# SparkFun_ZED-F9R_v12_uFL.net
KiCad netlist of a schematic drawn in EAGLE
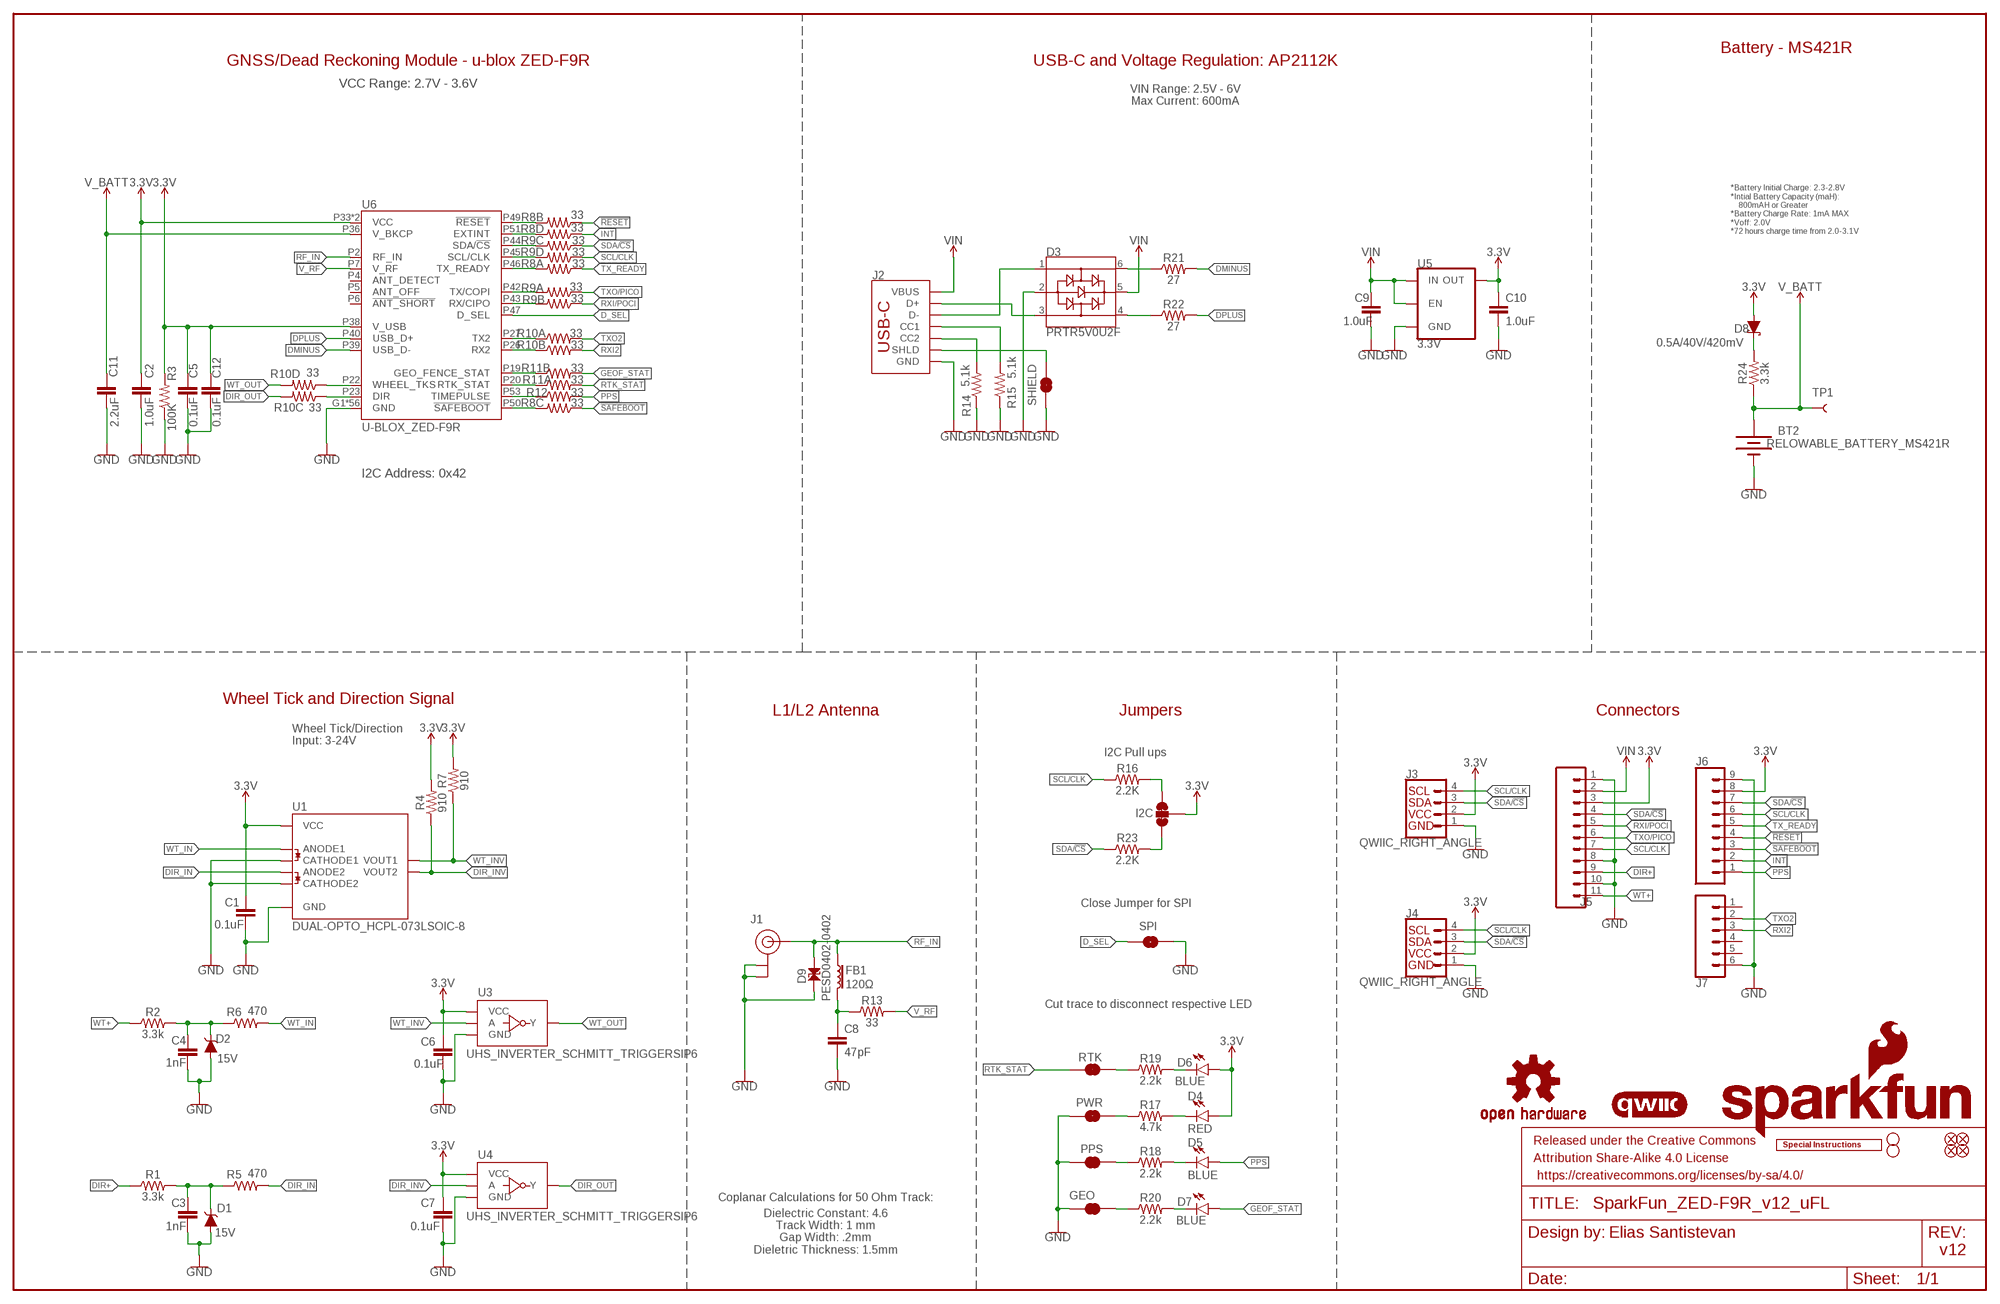
[diagram p0: schematic, sheet 1]

(export (version "E")
  (design (tool "Eeschema 10.0.6"))
  (components
    (comp (ref "$1_25_$_2020-03-30_22-52-05")
      (value "STAND-OFFTIGHT")
      (footprint "eagle-import:STAND-OFF-TIGHT")
      (libsource (lib "eagle-import") (part "STAND-OFFTIGHT"))
    )
    (comp (ref "BT2")
      (value "RELOWABLE_BATTERY_MS421R")
      (footprint "eagle-import:MS421R_IV03E")
      (libsource (lib "eagle-import") (part "RELOWABLE_BATTERY_MS421R"))
    )
    (comp (ref "C1")
      (value "0.1uF")
      (footprint "eagle-import:0402-TIGHT")
      (libsource (lib "eagle-import") (part "0.1UF-0402T-6.3V-10%-X7R"))
    )
    (comp (ref "C2")
      (value "1.0uF")
      (footprint "eagle-import:0402-TIGHT")
      (libsource (lib "eagle-import") (part "1.0UF-0402T-16V-10%"))
    )
    (comp (ref "C3")
      (value "1nF")
      (footprint "eagle-import:0402")
      (libsource (lib "eagle-import") (part "1.0NF/1000PF-0402-25V-10%-X7R"))
    )
    (comp (ref "C4")
      (value "1nF")
      (footprint "eagle-import:0402")
      (libsource (lib "eagle-import") (part "1.0NF/1000PF-0402-25V-10%-X7R"))
    )
    (comp (ref "C5")
      (value "0.1uF")
      (footprint "eagle-import:0402-TIGHT")
      (libsource (lib "eagle-import") (part "0.1UF-0402T-6.3V-10%-X7R"))
    )
    (comp (ref "C6")
      (value "0.1uF")
      (footprint "eagle-import:0402-TIGHT")
      (libsource (lib "eagle-import") (part "0.1UF-0402T-6.3V-10%-X7R"))
    )
    (comp (ref "C7")
      (value "0.1uF")
      (footprint "eagle-import:0402-TIGHT")
      (libsource (lib "eagle-import") (part "0.1UF-0402T-6.3V-10%-X7R"))
    )
    (comp (ref "C8")
      (value "47pF")
      (footprint "eagle-import:0402")
      (libsource (lib "eagle-import") (part "47PF-0402-25V-5%-X7R"))
    )
    (comp (ref "C9")
      (value "1.0uF")
      (footprint "eagle-import:0402-TIGHT")
      (libsource (lib "eagle-import") (part "1.0UF-0402T-16V-10%"))
    )
    (comp (ref "C10")
      (value "1.0uF")
      (footprint "eagle-import:0402-TIGHT")
      (libsource (lib "eagle-import") (part "1.0UF-0402T-16V-10%"))
    )
    (comp (ref "C11")
      (value "2.2uF")
      (footprint "eagle-import:0402-TIGHT")
      (libsource (lib "eagle-import") (part "2.2UF-0402_TIGHT-10V-10%-X5R"))
    )
    (comp (ref "C12")
      (value "0.1uF")
      (footprint "eagle-import:0402-TIGHT")
      (libsource (lib "eagle-import") (part "0.1UF-0402T-6.3V-10%-X7R"))
    )
    (comp (ref "D1")
      (value "15V")
      (footprint "eagle-import:SOT23-3")
      (libsource (lib "eagle-import") (part "DIODE-ZENER-BZX84C15LT3G"))
    )
    (comp (ref "D2")
      (value "15V")
      (footprint "eagle-import:SOT23-3")
      (libsource (lib "eagle-import") (part "DIODE-ZENER-BZX84C15LT3G"))
    )
    (comp (ref "D3")
      (value "PRTR5V0U2F")
      (footprint "eagle-import:SOT886")
      (libsource (lib "eagle-import") (part "PRTR5V0U2F"))
    )
    (comp (ref "D4")
      (value "RED")
      (footprint "eagle-import:LED-0603")
      (libsource (lib "eagle-import") (part "LED-RED_0603-KB"))
    )
    (comp (ref "D5")
      (value "BLUE")
      (footprint "eagle-import:LED-0603")
      (libsource (lib "eagle-import") (part "LED-BLUE0603"))
    )
    (comp (ref "D6")
      (value "BLUE")
      (footprint "eagle-import:LED-0603")
      (libsource (lib "eagle-import") (part "LED-BLUE0603"))
    )
    (comp (ref "D7")
      (value "BLUE")
      (footprint "eagle-import:LED-0603")
      (libsource (lib "eagle-import") (part "LED-BLUE0603"))
    )
    (comp (ref "D8")
      (value "0.5A/40V/420mV")
      (footprint "eagle-import:SOD-323")
      (libsource (lib "eagle-import") (part "DIODE-SCHOTTKY-PMEG4005EJ"))
    )
    (comp (ref "D9")
      (value "PESD0402-0402")
      (footprint "eagle-import:0402")
      (fields
        (field (name "DIGIKEY_PART") "PESD0402-140CT-ND")
        (field (name "MOUSE_PART") "650-PESD0402-140")
      )
      (libsource (lib "eagle-import") (part "PESD0402-0402"))
    )
    (comp (ref "FB1")
      (value "120Ω")
      (footprint "eagle-import:0402")
      (fields (field (name "MFG_PART") "BLM15HB121SN1D"))
      (libsource (lib "eagle-import") (part "FERRITE_BEAD-120_OHM-0402"))
    )
    (comp (ref "FD1")
      (value "FIDUCIALUFIDUCIAL")
      (footprint "eagle-import:FIDUCIAL-MICRO")
      (libsource (lib "eagle-import") (part "FIDUCIALUFIDUCIAL"))
    )
    (comp (ref "FD2")
      (value "FIDUCIALUFIDUCIAL")
      (footprint "eagle-import:FIDUCIAL-MICRO")
      (libsource (lib "eagle-import") (part "FIDUCIALUFIDUCIAL"))
    )
    (comp (ref "FD3")
      (value "FIDUCIALUFIDUCIAL")
      (footprint "eagle-import:FIDUCIAL-MICRO")
      (libsource (lib "eagle-import") (part "FIDUCIALUFIDUCIAL"))
    )
    (comp (ref "FD4")
      (value "FIDUCIALUFIDUCIAL")
      (footprint "eagle-import:FIDUCIAL-MICRO")
      (libsource (lib "eagle-import") (part "FIDUCIALUFIDUCIAL"))
    )
    (comp (ref "FRAME1")
      (value "FRAME-LEDGER")
      (footprint "eagle-import:CREATIVE_COMMONS")
      (libsource (lib "eagle-import") (part "FRAME-LEDGER"))
    )
    (comp (ref "GEO")
      (value "JUMPER-SMT_2_NC_TRACE_SILK")
      (footprint "eagle-import:SMT-JUMPER_2_NC_TRACE_SILK")
      (libsource (lib "eagle-import") (part "JUMPER-SMT_2_NC_TRACE_SILK"))
    )
    (comp (ref "H2")
      (value "STAND-OFFTIGHT")
      (footprint "eagle-import:STAND-OFF-TIGHT")
      (libsource (lib "eagle-import") (part "STAND-OFFTIGHT"))
    )
    (comp (ref "I2C")
      (value "JUMPER-SMT_3_2-NC_TRACE_SILK")
      (footprint "eagle-import:SMT-JUMPER_3_2-NC_TRACE_SILK")
      (libsource (lib "eagle-import") (part "JUMPER-SMT_3_2-NC_TRACE_SILK"))
    )
    (comp (ref "J1")
      (value "U.FL")
      (footprint "eagle-import:U.FL")
      (libsource (lib "eagle-import") (part "U.FL"))
    )
    (comp (ref "J2")
      (value "USB_C_2-LAYER_PADS")
      (footprint "eagle-import:USB-C-16P-2LAYER-PADS")
      (libsource (lib "eagle-import") (part "USB_C_2-LAYER_PADS"))
    )
    (comp (ref "J3")
      (value "QWIIC_RIGHT_ANGLE")
      (footprint "eagle-import:JST04_1MM_RA")
      (libsource (lib "eagle-import") (part "QWIIC_CONNECTORJS-1MM"))
    )
    (comp (ref "J4")
      (value "QWIIC_RIGHT_ANGLE")
      (footprint "eagle-import:JST04_1MM_RA")
      (libsource (lib "eagle-import") (part "QWIIC_CONNECTORJS-1MM"))
    )
    (comp (ref "J5")
      (value "CONN_111X11_NO_SILK")
      (footprint "eagle-import:1X11_NO_SILK")
      (libsource (lib "eagle-import") (part "CONN_111X11_NO_SILK"))
    )
    (comp (ref "J6")
      (value "CONN_09NO_SILK")
      (footprint "eagle-import:1X09_NO_SILK")
      (libsource (lib "eagle-import") (part "CONN_09NO_SILK"))
    )
    (comp (ref "J7")
      (value "CONN_06NO_SILK_NO_POP")
      (footprint "eagle-import:1X06_NO_SILK")
      (libsource (lib "eagle-import") (part "CONN_06NO_SILK_NO_POP"))
    )
    (comp (ref "LOGO1")
      (value "OSHW-LOGOS")
      (footprint "eagle-import:OSHW-LOGO-S")
      (libsource (lib "eagle-import") (part "OSHW-LOGOS"))
    )
    (comp (ref "LOGO2")
      (value "QWIIC_LOGO_4MM")
      (footprint "eagle-import:QWIIC_4MM")
      (libsource (lib "eagle-import") (part "QWIIC_LOGO_4MM"))
    )
    (comp (ref "LOGO3")
      (value "SFE_LOGO_NAME_FLAME.2_INCH")
      (footprint "eagle-import:SFE_LOGO_NAME_FLAME_.2")
      (libsource (lib "eagle-import") (part "SFE_LOGO_NAME_FLAME.2_INCH"))
    )
    (comp (ref "LOGO5")
      (value "SPECIAL_INSTRUCTIONS-ORDERING")
      (footprint "eagle-import:ORDERING_INSTRUCTIONS")
      (libsource (lib "eagle-import") (part "SPECIAL_INSTRUCTIONS-ORDERING"))
    )
    (comp (ref "PPS")
      (value "JUMPER-SMT_2_NC_TRACE_SILK")
      (footprint "eagle-import:SMT-JUMPER_2_NC_TRACE_SILK")
      (libsource (lib "eagle-import") (part "JUMPER-SMT_2_NC_TRACE_SILK"))
    )
    (comp (ref "PWR")
      (value "JUMPER-SMT_2_NC_TRACE_SILK")
      (footprint "eagle-import:SMT-JUMPER_2_NC_TRACE_SILK")
      (libsource (lib "eagle-import") (part "JUMPER-SMT_2_NC_TRACE_SILK"))
    )
    (comp (ref "R1")
      (value "3.3k")
      (footprint "eagle-import:0603")
      (libsource (lib "eagle-import") (part "3.3KOHM-0603-1/10W-1%"))
    )
    (comp (ref "R2")
      (value "3.3k")
      (footprint "eagle-import:0603")
      (libsource (lib "eagle-import") (part "3.3KOHM-0603-1/10W-1%"))
    )
    (comp (ref "R3")
      (value "100K")
      (footprint "eagle-import:0402")
      (libsource (lib "eagle-import") (part "100KOHM-0402-1/16W-1%"))
    )
    (comp (ref "R4")
      (value "910")
      (footprint "eagle-import:0603")
      (libsource (lib "eagle-import") (part "910OHM-0603-1/10W-5%"))
    )
    (comp (ref "R5")
      (value "470")
      (footprint "eagle-import:0603")
      (libsource (lib "eagle-import") (part "470OHM-0603-1/10W-1%"))
    )
    (comp (ref "R6")
      (value "470")
      (footprint "eagle-import:0603")
      (libsource (lib "eagle-import") (part "470OHM-0603-1/10W-1%"))
    )
    (comp (ref "R7")
      (value "910")
      (footprint "eagle-import:0603")
      (libsource (lib "eagle-import") (part "910OHM-0603-1/10W-5%"))
    )
    (comp (ref "R8")
      (value "33")
      (footprint "eagle-import:1206_RA")
      (libsource (lib "eagle-import") (part "33OHM_RA-1206-1/16W-5%"))
    )
    (comp (ref "R9")
      (value "33")
      (footprint "eagle-import:1206_RA")
      (libsource (lib "eagle-import") (part "33OHM_RA-1206-1/16W-5%"))
    )
    (comp (ref "R10")
      (value "33")
      (footprint "eagle-import:1206_RA")
      (libsource (lib "eagle-import") (part "33OHM_RA-1206-1/16W-5%"))
    )
    (comp (ref "R11")
      (value "33")
      (footprint "eagle-import:1206_RA")
      (libsource (lib "eagle-import") (part "33OHM_RA-1206-1/16W-5%"))
    )
    (comp (ref "R12")
      (value "33")
      (footprint "eagle-import:0603")
      (libsource (lib "eagle-import") (part "33OHM-0603-1/10W-1%"))
    )
    (comp (ref "R13")
      (value "33")
      (footprint "eagle-import:0603")
      (libsource (lib "eagle-import") (part "33OHM-0603-1/10W-1%"))
    )
    (comp (ref "R14")
      (value "5.1k")
      (footprint "eagle-import:0402")
      (libsource (lib "eagle-import") (part "5.1KOHM-0402-1/16W-1%"))
    )
    (comp (ref "R15")
      (value "5.1k")
      (footprint "eagle-import:0402")
      (libsource (lib "eagle-import") (part "5.1KOHM-0402-1/16W-1%"))
    )
    (comp (ref "R16")
      (value "2.2K")
      (footprint "eagle-import:0402")
      (libsource (lib "eagle-import") (part "2.2KOHM-0402-1/16W-1%"))
    )
    (comp (ref "R17")
      (value "4.7k")
      (footprint "eagle-import:0603")
      (libsource (lib "eagle-import") (part "4.7KOHM-0603-1/10W-1%"))
    )
    (comp (ref "R18")
      (value "2.2k")
      (footprint "eagle-import:0603")
      (libsource (lib "eagle-import") (part "2.2KOHM-0603-1/10W-1%"))
    )
    (comp (ref "R19")
      (value "2.2k")
      (footprint "eagle-import:0603")
      (libsource (lib "eagle-import") (part "2.2KOHM-0603-1/10W-1%"))
    )
    (comp (ref "R20")
      (value "2.2k")
      (footprint "eagle-import:0603")
      (libsource (lib "eagle-import") (part "2.2KOHM-0603-1/10W-1%"))
    )
    (comp (ref "R21")
      (value "27")
      (footprint "eagle-import:0603")
      (libsource (lib "eagle-import") (part "27OHM-0603-1/10W-1%"))
    )
    (comp (ref "R22")
      (value "27")
      (footprint "eagle-import:0603")
      (libsource (lib "eagle-import") (part "27OHM-0603-1/10W-1%"))
    )
    (comp (ref "R23")
      (value "2.2K")
      (footprint "eagle-import:0402")
      (libsource (lib "eagle-import") (part "2.2KOHM-0402-1/16W-1%"))
    )
    (comp (ref "R24")
      (value "3.3k")
      (footprint "eagle-import:0603")
      (libsource (lib "eagle-import") (part "3.3KOHM-0603-1/10W-1%"))
    )
    (comp (ref "RTK")
      (value "JUMPER-SMT_2_NC_TRACE_SILK")
      (footprint "eagle-import:SMT-JUMPER_2_NC_TRACE_SILK")
      (libsource (lib "eagle-import") (part "JUMPER-SMT_2_NC_TRACE_SILK"))
    )
    (comp (ref "SHIELD")
      (value "JUMPER-SMT_2_NC_TRACE_SILK")
      (footprint "eagle-import:SMT-JUMPER_2_NC_TRACE_SILK")
      (libsource (lib "eagle-import") (part "JUMPER-SMT_2_NC_TRACE_SILK"))
    )
    (comp (ref "SPI")
      (value "JUMPER-SMT_2_NO_SILK")
      (footprint "eagle-import:SMT-JUMPER_2_NO_SILK")
      (libsource (lib "eagle-import") (part "JUMPER-SMT_2_NO_SILK"))
    )
    (comp (ref "TP1")
      (value "TEST-POINT3X5")
      (footprint "eagle-import:PAD.03X.05")
      (libsource (lib "eagle-import") (part "TEST-POINT3X5"))
    )
    (comp (ref "U1")
      (value "DUAL-OPTO_HCPL-073LSOIC-8")
      (footprint "eagle-import:SO08")
      (libsource (lib "eagle-import") (part "DUAL-OPTO_HCPL-073LSOIC-8"))
    )
    (comp (ref "U3")
      (value "UHS_INVERTER_SCHMITT_TRIGGERSIP6")
      (footprint "eagle-import:SIP6_MICROPAK2")
      (libsource (lib "eagle-import") (part "UHS_INVERTER_SCHMITT_TRIGGER_MPAK2"))
    )
    (comp (ref "U4")
      (value "UHS_INVERTER_SCHMITT_TRIGGERSIP6")
      (footprint "eagle-import:SIP6_MICROPAK2")
      (libsource (lib "eagle-import") (part "UHS_INVERTER_SCHMITT_TRIGGER_MPAK2"))
    )
    (comp (ref "U5")
      (value "3.3V")
      (footprint "eagle-import:SOT23-5")
      (libsource (lib "eagle-import") (part "V_REG_AP2112K-3.3V"))
    )
    (comp (ref "U6")
      (value "U-BLOX_ZED-F9R")
      (footprint "eagle-import:UBLOX_ZED_F9R")
      (libsource (lib "eagle-import") (part "U-BLOX_ZED-F9R"))
    )
  )
  (nets
    (net (code "1") (name "/SDA{slash}~{CS}") (class "Default")
      (node (ref "J3") (pin "3") (pinfunction "3_3") (pintype "passive"))
      (node (ref "J4") (pin "3") (pinfunction "3_3") (pintype "passive"))
      (node (ref "J5") (pin "4") (pinfunction "4_4") (pintype "passive"))
      (node (ref "J6") (pin "7") (pinfunction "7_7") (pintype "passive"))
      (node (ref "R23") (pin "1") (pinfunction "1_1") (pintype "passive"))
      (node (ref "R9") (pin "P3") (pinfunction "1_P3") (pintype "passive"))
    )
    (net (code "2") (name "/~{RESET}") (class "Default")
      (node (ref "J6") (pin "4") (pinfunction "4_4") (pintype "passive"))
      (node (ref "R8") (pin "P2") (pinfunction "1_P2") (pintype "passive"))
    )
    (net (code "3") (name "/~{SAFEBOOT}") (class "Default")
      (node (ref "J6") (pin "3") (pinfunction "3_3") (pintype "passive"))
      (node (ref "R8") (pin "P3") (pinfunction "1_P3") (pintype "passive"))
    )
    (net (code "4") (name "3.3V") (class "Default")
      (node (ref "C1") (pin "1") (pinfunction "1_1") (pintype "passive"))
      (node (ref "C10") (pin "1") (pinfunction "1_1") (pintype "passive"))
      (node (ref "C12") (pin "1") (pinfunction "1_1") (pintype "passive"))
      (node (ref "C2") (pin "1") (pinfunction "1_1") (pintype "passive"))
      (node (ref "C5") (pin "1") (pinfunction "1_1") (pintype "passive"))
      (node (ref "C6") (pin "1") (pinfunction "1_1") (pintype "passive"))
      (node (ref "C7") (pin "1") (pinfunction "1_1") (pintype "passive"))
      (node (ref "D4") (pin "A") (pinfunction "A_A") (pintype "passive"))
      (node (ref "D6") (pin "A") (pinfunction "A_A") (pintype "passive"))
      (node (ref "D8") (pin "A") (pinfunction "A_A") (pintype "passive"))
      (node (ref "I2C") (pin "2") (pinfunction "2_2") (pintype "passive"))
      (node (ref "J3") (pin "2") (pinfunction "2_2") (pintype "power_in"))
      (node (ref "J4") (pin "2") (pinfunction "2_2") (pintype "power_in"))
      (node (ref "J5") (pin "3") (pinfunction "3_3") (pintype "passive"))
      (node (ref "J6") (pin "8") (pinfunction "8_8") (pintype "passive"))
      (node (ref "R3") (pin "2") (pinfunction "2_2") (pintype "passive"))
      (node (ref "R4") (pin "2") (pinfunction "2_2") (pintype "passive"))
      (node (ref "R7") (pin "2") (pinfunction "2_2") (pintype "passive"))
      (node (ref "U1") (pin "8") (pinfunction "VCC_8") (pintype "power_in"))
      (node (ref "U3") (pin "P6") (pinfunction "VCC_P6") (pintype "power_in"))
      (node (ref "U4") (pin "P6") (pinfunction "VCC_P6") (pintype "power_in"))
      (node (ref "U5") (pin "5") (pinfunction "OUT_5") (pintype "passive"))
      (node (ref "U6") (pin "P33") (pinfunction "VCC_P33") (pintype "power_in"))
      (node (ref "U6") (pin "P34") (pinfunction "VCC_P34") (pintype "power_in"))
      (node (ref "U6") (pin "P38") (pinfunction "V_USB_P38") (pintype "power_in"))
    )
    (net (code "5") (name "DIR+") (class "Default")
      (node (ref "J5") (pin "9") (pinfunction "9_9") (pintype "passive"))
      (node (ref "R1") (pin "1") (pinfunction "1_1") (pintype "passive"))
    )
    (net (code "6") (name "DIR_IN") (class "Default")
      (node (ref "R5") (pin "2") (pinfunction "2_2") (pintype "passive"))
      (node (ref "U1") (pin "4") (pinfunction "ANODE2_4") (pintype "input"))
    )
    (net (code "7") (name "DIR_INV") (class "Default")
      (node (ref "R4") (pin "1") (pinfunction "1_1") (pintype "passive"))
      (node (ref "U1") (pin "6") (pinfunction "VOUT2_6") (pintype "output"))
      (node (ref "U4") (pin "P2") (pinfunction "A_P2") (pintype "input"))
    )
    (net (code "8") (name "DIR_OUT") (class "Default")
      (node (ref "R10") (pin "P6") (pinfunction "2_P6") (pintype "passive"))
      (node (ref "U4") (pin "P4") (pinfunction "Y_P4") (pintype "output"))
    )
    (net (code "9") (name "DMINUS") (class "Default")
      (node (ref "R21") (pin "2") (pinfunction "2_2") (pintype "passive"))
      (node (ref "U6") (pin "P39") (pinfunction "USB_D-_P39") (pintype "bidirectional"))
    )
    (net (code "10") (name "DPLUS") (class "Default")
      (node (ref "R22") (pin "2") (pinfunction "2_2") (pintype "passive"))
      (node (ref "U6") (pin "P40") (pinfunction "USB_D+_P40") (pintype "bidirectional"))
    )
    (net (code "11") (name "D_SEL") (class "Default")
      (node (ref "SPI") (pin "1") (pinfunction "1_1") (pintype "passive"))
      (node (ref "U6") (pin "P47") (pinfunction "D_SEL_P47") (pintype "bidirectional"))
    )
    (net (code "12") (name "GEOF_STAT") (class "Default")
      (node (ref "D7") (pin "A") (pinfunction "A_A") (pintype "passive"))
      (node (ref "R11") (pin "P7") (pinfunction "2_P7") (pintype "passive"))
    )
    (net (code "13") (name "GND") (class "Default")
      (node (ref "BT2") (pin "-") (pinfunction "-_-") (pintype "power_in"))
      (node (ref "C1") (pin "2") (pinfunction "2_2") (pintype "passive"))
      (node (ref "C10") (pin "2") (pinfunction "2_2") (pintype "passive"))
      (node (ref "C11") (pin "2") (pinfunction "2_2") (pintype "passive"))
      (node (ref "C12") (pin "2") (pinfunction "2_2") (pintype "passive"))
      (node (ref "C2") (pin "2") (pinfunction "2_2") (pintype "passive"))
      (node (ref "C3") (pin "2") (pinfunction "2_2") (pintype "passive"))
      (node (ref "C4") (pin "2") (pinfunction "2_2") (pintype "passive"))
      (node (ref "C5") (pin "2") (pinfunction "2_2") (pintype "passive"))
      (node (ref "C6") (pin "2") (pinfunction "2_2") (pintype "passive"))
      (node (ref "C7") (pin "2") (pinfunction "2_2") (pintype "passive"))
      (node (ref "C8") (pin "2") (pinfunction "2_2") (pintype "passive"))
      (node (ref "C9") (pin "2") (pinfunction "2_2") (pintype "passive"))
      (node (ref "D1") (pin "1") (pinfunction "A_1") (pintype "passive"))
      (node (ref "D2") (pin "1") (pinfunction "A_1") (pintype "passive"))
      (node (ref "D3") (pin "2") (pinfunction "2_2") (pintype "power_in"))
      (node (ref "D9") (pin "1") (pinfunction "1_1") (pintype "bidirectional"))
      (node (ref "GEO") (pin "1") (pinfunction "1_1") (pintype "passive"))
      (node (ref "J1") (pin "1") (pinfunction "GND_1") (pintype "bidirectional"))
      (node (ref "J1") (pin "2") (pinfunction "GND_2") (pintype "bidirectional"))
      (node (ref "J2") (pin "GND") (pinfunction "GND_GND") (pintype "bidirectional"))
      (node (ref "J2") (pin "GND2") (pinfunction "GND_GND2") (pintype "bidirectional"))
      (node (ref "J3") (pin "1") (pinfunction "1_1") (pintype "power_in"))
      (node (ref "J4") (pin "1") (pinfunction "1_1") (pintype "power_in"))
      (node (ref "J5") (pin "1") (pinfunction "1_1") (pintype "passive"))
      (node (ref "J5") (pin "10") (pinfunction "10_10") (pintype "passive"))
      (node (ref "J5") (pin "8") (pinfunction "8_8") (pintype "passive"))
      (node (ref "J6") (pin "9") (pinfunction "9_9") (pintype "passive"))
      (node (ref "J7") (pin "6") (pinfunction "6_6") (pintype "passive"))
      (node (ref "PPS") (pin "1") (pinfunction "1_1") (pintype "passive"))
      (node (ref "PWR") (pin "1") (pinfunction "1_1") (pintype "passive"))
      (node (ref "R14") (pin "1") (pinfunction "1_1") (pintype "passive"))
      (node (ref "R15") (pin "1") (pinfunction "1_1") (pintype "passive"))
      (node (ref "R3") (pin "1") (pinfunction "1_1") (pintype "passive"))
      (node (ref "SHIELD") (pin "1") (pinfunction "1_1") (pintype "passive"))
      (node (ref "SPI") (pin "2") (pinfunction "2_2") (pintype "passive"))
      (node (ref "U1") (pin "2") (pinfunction "CATHODE1_2") (pintype "input"))
      (node (ref "U1") (pin "3") (pinfunction "CATHODE2_3") (pintype "input"))
      (node (ref "U1") (pin "5") (pinfunction "GND_5") (pintype "power_in"))
      (node (ref "U3") (pin "P3") (pinfunction "GND_P3") (pintype "power_in"))
      (node (ref "U4") (pin "P3") (pinfunction "GND_P3") (pintype "power_in"))
      (node (ref "U5") (pin "2") (pinfunction "GND_2") (pintype "input"))
      (node (ref "U6") (pin "G1") (pinfunction "GND_G1") (pintype "power_in"))
      (node (ref "U6") (pin "G10") (pinfunction "GND_G10") (pintype "power_in"))
      (node (ref "U6") (pin "G11") (pinfunction "GND_G11") (pintype "power_in"))
      (node (ref "U6") (pin "G12") (pinfunction "GND_G12") (pintype "power_in"))
      (node (ref "U6") (pin "G13") (pinfunction "GND_G13") (pintype "power_in"))
      (node (ref "U6") (pin "G14") (pinfunction "GND_G14") (pintype "power_in"))
      (node (ref "U6") (pin "G15") (pinfunction "GND_G15") (pintype "power_in"))
      (node (ref "U6") (pin "G16") (pinfunction "GND_G16") (pintype "power_in"))
      (node (ref "U6") (pin "G17") (pinfunction "GND_G17") (pintype "power_in"))
      (node (ref "U6") (pin "G18") (pinfunction "GND_G18") (pintype "power_in"))
      (node (ref "U6") (pin "G19") (pinfunction "GND_G19") (pintype "power_in"))
      (node (ref "U6") (pin "G2") (pinfunction "GND_G2") (pintype "power_in"))
      (node (ref "U6") (pin "G20") (pinfunction "GND_G20") (pintype "power_in"))
      (node (ref "U6") (pin "G21") (pinfunction "GND_G21") (pintype "power_in"))
      (node (ref "U6") (pin "G22") (pinfunction "GND_G22") (pintype "power_in"))
      (node (ref "U6") (pin "G23") (pinfunction "GND_G23") (pintype "power_in"))
      (node (ref "U6") (pin "G24") (pinfunction "GND_G24") (pintype "power_in"))
      (node (ref "U6") (pin "G25") (pinfunction "GND_G25") (pintype "power_in"))
      (node (ref "U6") (pin "G26") (pinfunction "GND_G26") (pintype "power_in"))
      (node (ref "U6") (pin "G27") (pinfunction "GND_G27") (pintype "power_in"))
      (node (ref "U6") (pin "G28") (pinfunction "GND_G28") (pintype "power_in"))
      (node (ref "U6") (pin "G29") (pinfunction "GND_G29") (pintype "power_in"))
      (node (ref "U6") (pin "G3") (pinfunction "GND_G3") (pintype "power_in"))
      (node (ref "U6") (pin "G30") (pinfunction "GND_G30") (pintype "power_in"))
      (node (ref "U6") (pin "G31") (pinfunction "GND_G31") (pintype "power_in"))
      (node (ref "U6") (pin "G32") (pinfunction "GND_G32") (pintype "power_in"))
      (node (ref "U6") (pin "G33") (pinfunction "GND_G33") (pintype "power_in"))
      (node (ref "U6") (pin "G34") (pinfunction "GND_G34") (pintype "power_in"))
      (node (ref "U6") (pin "G35") (pinfunction "GND_G35") (pintype "power_in"))
      (node (ref "U6") (pin "G36") (pinfunction "GND_G36") (pintype "power_in"))
      (node (ref "U6") (pin "G37") (pinfunction "GND_G37") (pintype "power_in"))
      (node (ref "U6") (pin "G38") (pinfunction "GND_G38") (pintype "power_in"))
      (node (ref "U6") (pin "G39") (pinfunction "GND_G39") (pintype "power_in"))
      (node (ref "U6") (pin "G4") (pinfunction "GND_G4") (pintype "power_in"))
      (node (ref "U6") (pin "G40") (pinfunction "GND_G40") (pintype "power_in"))
      (node (ref "U6") (pin "G41") (pinfunction "GND_G41") (pintype "power_in"))
      (node (ref "U6") (pin "G42") (pinfunction "GND_G42") (pintype "power_in"))
      (node (ref "U6") (pin "G43") (pinfunction "GND_G43") (pintype "power_in"))
      (node (ref "U6") (pin "G44") (pinfunction "GND_G44") (pintype "power_in"))
      (node (ref "U6") (pin "G45") (pinfunction "GND_G45") (pintype "power_in"))
      (node (ref "U6") (pin "G46") (pinfunction "GND_G46") (pintype "power_in"))
      (node (ref "U6") (pin "G47") (pinfunction "GND_G47") (pintype "power_in"))
      (node (ref "U6") (pin "G48") (pinfunction "GND_G48") (pintype "power_in"))
      (node (ref "U6") (pin "G5") (pinfunction "GND_G5") (pintype "power_in"))
      (node (ref "U6") (pin "G6") (pinfunction "GND_G6") (pintype "power_in"))
      (node (ref "U6") (pin "G7") (pinfunction "GND_G7") (pintype "power_in"))
      (node (ref "U6") (pin "G8") (pinfunction "GND_G8") (pintype "power_in"))
      (node (ref "U6") (pin "G9") (pinfunction "GND_G9") (pintype "power_in"))
      (node (ref "U6") (pin "P1") (pinfunction "GND_P1") (pintype "power_in"))
      (node (ref "U6") (pin "P12") (pinfunction "GND_P12") (pintype "power_in"))
      (node (ref "U6") (pin "P14") (pinfunction "GND_P14") (pintype "power_in"))
      (node (ref "U6") (pin "P3") (pinfunction "GND_P3") (pintype "power_in"))
      (node (ref "U6") (pin "P32") (pinfunction "GND_P32") (pintype "power_in"))
      (node (ref "U6") (pin "P37") (pinfunction "GND_P37") (pintype "power_in"))
      (node (ref "U6") (pin "P41") (pinfunction "GND_P41") (pintype "power_in"))
      (node (ref "U6") (pin "P48") (pinfunction "GND_P48") (pintype "power_in"))
    )
    (net (code "14") (name "INT") (class "Default")
      (node (ref "J6") (pin "2") (pinfunction "2_2") (pintype "passive"))
      (node (ref "R8") (pin "P4") (pinfunction "1_P4") (pintype "passive"))
    )
    (net (code "15") (name "Net-(C8-Pad1)") (class "Default")
      (node (ref "C8") (pin "1") (pinfunction "1_1") (pintype "passive"))
      (node (ref "FB1") (pin "2") (pinfunction "2_2") (pintype "passive"))
      (node (ref "R13") (pin "1") (pinfunction "1_1") (pintype "passive"))
    )
    (net (code "16") (name "Net-(D1-C)") (class "Default")
      (node (ref "C3") (pin "1") (pinfunction "1_1") (pintype "passive"))
      (node (ref "D1") (pin "3") (pinfunction "C_3") (pintype "passive"))
      (node (ref "R1") (pin "2") (pinfunction "2_2") (pintype "passive"))
      (node (ref "R5") (pin "1") (pinfunction "1_1") (pintype "passive"))
    )
    (net (code "17") (name "Net-(D2-C)") (class "Default")
      (node (ref "C4") (pin "1") (pinfunction "1_1") (pintype "passive"))
      (node (ref "D2") (pin "3") (pinfunction "C_3") (pintype "passive"))
      (node (ref "R2") (pin "2") (pinfunction "2_2") (pintype "passive"))
      (node (ref "R6") (pin "1") (pinfunction "1_1") (pintype "passive"))
    )
    (net (code "18") (name "Net-(D3-Pad1)") (class "Default")
      (node (ref "D3") (pin "1") (pinfunction "1_1") (pintype "bidirectional"))
      (node (ref "J2") (pin "A7") (pinfunction "D-_A7") (pintype "bidirectional"))
      (node (ref "J2") (pin "B7") (pinfunction "D-_B7") (pintype "bidirectional"))
    )
    (net (code "19") (name "Net-(D3-Pad3)") (class "Default")
      (node (ref "D3") (pin "3") (pinfunction "3_3") (pintype "bidirectional"))
      (node (ref "J2") (pin "A6") (pinfunction "D+_A6") (pintype "bidirectional"))
      (node (ref "J2") (pin "B6") (pinfunction "D+_B6") (pintype "bidirectional"))
    )
    (net (code "20") (name "Net-(D3-Pad4)") (class "Default")
      (node (ref "D3") (pin "4") (pinfunction "4_4") (pintype "bidirectional"))
      (node (ref "R22") (pin "1") (pinfunction "1_1") (pintype "passive"))
    )
    (net (code "21") (name "Net-(D3-Pad6)") (class "Default")
      (node (ref "D3") (pin "6") (pinfunction "6_6") (pintype "bidirectional"))
      (node (ref "R21") (pin "1") (pinfunction "1_1") (pintype "passive"))
    )
    (net (code "22") (name "Net-(D4-PadC)") (class "Default")
      (node (ref "D4") (pin "C") (pinfunction "C_C") (pintype "passive"))
      (node (ref "R17") (pin "2") (pinfunction "2_2") (pintype "passive"))
    )
    (net (code "23") (name "Net-(D5-PadC)") (class "Default")
      (node (ref "D5") (pin "C") (pinfunction "C_C") (pintype "passive"))
      (node (ref "R18") (pin "2") (pinfunction "2_2") (pintype "passive"))
    )
    (net (code "24") (name "Net-(D6-PadC)") (class "Default")
      (node (ref "D6") (pin "C") (pinfunction "C_C") (pintype "passive"))
      (node (ref "R19") (pin "2") (pinfunction "2_2") (pintype "passive"))
    )
    (net (code "25") (name "Net-(D7-PadC)") (class "Default")
      (node (ref "D7") (pin "C") (pinfunction "C_C") (pintype "passive"))
      (node (ref "R20") (pin "2") (pinfunction "2_2") (pintype "passive"))
    )
    (net (code "26") (name "Net-(D8-PadC)") (class "Default")
      (node (ref "D8") (pin "C") (pinfunction "C_C") (pintype "passive"))
      (node (ref "R24") (pin "2") (pinfunction "2_2") (pintype "passive"))
    )
    (net (code "27") (name "Net-(GEO-Pad2)") (class "Default")
      (node (ref "GEO") (pin "2") (pinfunction "2_2") (pintype "passive"))
      (node (ref "R20") (pin "1") (pinfunction "1_1") (pintype "passive"))
    )
    (net (code "28") (name "Net-(I2C-Pad1)") (class "Default")
      (node (ref "I2C") (pin "1") (pinfunction "1_1") (pintype "passive"))
      (node (ref "R23") (pin "2") (pinfunction "2_2") (pintype "passive"))
    )
    (net (code "29") (name "Net-(I2C-Pad3)") (class "Default")
      (node (ref "I2C") (pin "3") (pinfunction "3_3") (pintype "passive"))
      (node (ref "R16") (pin "2") (pinfunction "2_2") (pintype "passive"))
    )
    (net (code "30") (name "Net-(J2-CC1)") (class "Default")
      (node (ref "J2") (pin "A5") (pinfunction "CC1_A5") (pintype "bidirectional"))
      (node (ref "R15") (pin "2") (pinfunction "2_2") (pintype "passive"))
    )
    (net (code "31") (name "Net-(J2-CC2)") (class "Default")
      (node (ref "J2") (pin "B5") (pinfunction "CC2_B5") (pintype "bidirectional"))
      (node (ref "R14") (pin "2") (pinfunction "2_2") (pintype "passive"))
    )
    (net (code "32") (name "Net-(J2-SHLD-PadSHLD1)") (class "Default")
      (node (ref "J2") (pin "SHLD1") (pinfunction "SHLD_SHLD1") (pintype "bidirectional"))
      (node (ref "J2") (pin "SHLD2") (pinfunction "SHLD_SHLD2") (pintype "bidirectional"))
      (node (ref "J2") (pin "SHLD3") (pinfunction "SHLD_SHLD3") (pintype "bidirectional"))
      (node (ref "J2") (pin "SHLD4") (pinfunction "SHLD_SHLD4") (pintype "bidirectional"))
      (node (ref "SHIELD") (pin "2") (pinfunction "2_2") (pintype "passive"))
    )
    (net (code "33") (name "Net-(PPS-Pad2)") (class "Default")
      (node (ref "PPS") (pin "2") (pinfunction "2_2") (pintype "passive"))
      (node (ref "R18") (pin "1") (pinfunction "1_1") (pintype "passive"))
    )
    (net (code "34") (name "Net-(PWR-Pad2)") (class "Default")
      (node (ref "PWR") (pin "2") (pinfunction "2_2") (pintype "passive"))
      (node (ref "R17") (pin "1") (pinfunction "1_1") (pintype "passive"))
    )
    (net (code "35") (name "Net-(R8A-2)") (class "Default")
      (node (ref "R8") (pin "P8") (pinfunction "2_P8") (pintype "passive"))
      (node (ref "U6") (pin "P46") (pinfunction "TX_READY_P46") (pintype "bidirectional"))
    )
    (net (code "36") (name "Net-(R8B-2)") (class "Default")
      (node (ref "R8") (pin "P7") (pinfunction "2_P7") (pintype "passive"))
      (node (ref "U6") (pin "P49") (pinfunction "~{RESET}_P49") (pintype "bidirectional"))
    )
    (net (code "37") (name "Net-(R8C-2)") (class "Default")
      (node (ref "R8") (pin "P6") (pinfunction "2_P6") (pintype "passive"))
      (node (ref "U6") (pin "P50") (pinfunction "~{SAFEBOOT}_P50") (pintype "input"))
    )
    (net (code "38") (name "Net-(R8D-2)") (class "Default")
      (node (ref "R8") (pin "P5") (pinfunction "2_P5") (pintype "passive"))
      (node (ref "U6") (pin "P51") (pinfunction "EXTINT_P51") (pintype "bidirectional"))
    )
    (net (code "39") (name "Net-(R9A-2)") (class "Default")
      (node (ref "R9") (pin "P8") (pinfunction "2_P8") (pintype "passive"))
      (node (ref "U6") (pin "P42") (pinfunction "TX/COPI_P42") (pintype "bidirectional"))
    )
    (net (code "40") (name "Net-(R9B-2)") (class "Default")
      (node (ref "R9") (pin "P7") (pinfunction "2_P7") (pintype "passive"))
      (node (ref "U6") (pin "P43") (pinfunction "RX/CIPO_P43") (pintype "bidirectional"))
    )
    (net (code "41") (name "Net-(R9C-2)") (class "Default")
      (node (ref "R9") (pin "P6") (pinfunction "2_P6") (pintype "passive"))
      (node (ref "U6") (pin "P44") (pinfunction "SDA/~{CS}_P44") (pintype "bidirectional"))
    )
    (net (code "42") (name "Net-(R9D-2)") (class "Default")
      (node (ref "R9") (pin "P5") (pinfunction "2_P5") (pintype "passive"))
      (node (ref "U6") (pin "P45") (pinfunction "SCL/CLK_P45") (pintype "bidirectional"))
    )
    (net (code "43") (name "Net-(R10A-1)") (class "Default")
      (node (ref "R10") (pin "P1") (pinfunction "1_P1") (pintype "passive"))
      (node (ref "U6") (pin "P27") (pinfunction "TX2_P27") (pintype "output"))
    )
    (net (code "44") (name "Net-(R10B-1)") (class "Default")
      (node (ref "R10") (pin "P2") (pinfunction "1_P2") (pintype "passive"))
      (node (ref "U6") (pin "P26") (pinfunction "RX2_P26") (pintype "input"))
    )
    (net (code "45") (name "Net-(R10C-1)") (class "Default")
      (node (ref "R10") (pin "P3") (pinfunction "1_P3") (pintype "passive"))
      (node (ref "U6") (pin "P23") (pinfunction "DIR_P23") (pintype "input"))
    )
    (net (code "46") (name "Net-(R10D-1)") (class "Default")
      (node (ref "R10") (pin "P4") (pinfunction "1_P4") (pintype "passive"))
      (node (ref "U6") (pin "P22") (pinfunction "WHEEL_TKS_P22") (pintype "input"))
    )
    (net (code "47") (name "Net-(R11A-1)") (class "Default")
      (node (ref "R11") (pin "P1") (pinfunction "1_P1") (pintype "passive"))
      (node (ref "U6") (pin "P20") (pinfunction "RTK_STAT_P20") (pintype "output"))
    )
    (net (code "48") (name "Net-(R11B-1)") (class "Default")
      (node (ref "R11") (pin "P2") (pinfunction "1_P2") (pintype "passive"))
      (node (ref "U6") (pin "P19") (pinfunction "GEO_FENCE_STAT_P19") (pintype "output"))
    )
    (net (code "49") (name "Net-(R19-Pad1)") (class "Default")
      (node (ref "R19") (pin "1") (pinfunction "1_1") (pintype "passive"))
      (node (ref "RTK") (pin "2") (pinfunction "2_2") (pintype "passive"))
    )
    (net (code "50") (name "Net-(U6-TIMEPULSE)") (class "Default")
      (node (ref "R12") (pin "1") (pinfunction "1_1") (pintype "passive"))
      (node (ref "U6") (pin "P53") (pinfunction "TIMEPULSE_P53") (pintype "output"))
    )
    (net (code "51") (name "PPS") (class "Default")
      (node (ref "D5") (pin "A") (pinfunction "A_A") (pintype "passive"))
      (node (ref "J6") (pin "1") (pinfunction "1_1") (pintype "passive"))
      (node (ref "R12") (pin "2") (pinfunction "2_2") (pintype "passive"))
    )
    (net (code "52") (name "RF_IN") (class "Default")
      (node (ref "D9") (pin "2") (pinfunction "2_2") (pintype "bidirectional"))
      (node (ref "FB1") (pin "1") (pinfunction "1_1") (pintype "passive"))
      (node (ref "J1") (pin "FEED") (pinfunction "SIGNAL_FEED") (pintype "bidirectional"))
      (node (ref "U6") (pin "P2") (pinfunction "RF_IN_P2") (pintype "input"))
    )
    (net (code "53") (name "RTK_STAT") (class "Default")
      (node (ref "R11") (pin "P8") (pinfunction "2_P8") (pintype "passive"))
      (node (ref "RTK") (pin "1") (pinfunction "1_1") (pintype "passive"))
    )
    (net (code "54") (name "RXI2") (class "Default")
      (node (ref "J7") (pin "3") (pinfunction "3_3") (pintype "passive"))
      (node (ref "R10") (pin "P7") (pinfunction "2_P7") (pintype "passive"))
    )
    (net (code "55") (name "RXI{slash}POCI") (class "Default")
      (node (ref "J5") (pin "5") (pinfunction "5_5") (pintype "passive"))
      (node (ref "R9") (pin "P2") (pinfunction "1_P2") (pintype "passive"))
    )
    (net (code "56") (name "SCL{slash}CLK") (class "Default")
      (node (ref "J3") (pin "4") (pinfunction "4_4") (pintype "passive"))
      (node (ref "J4") (pin "4") (pinfunction "4_4") (pintype "passive"))
      (node (ref "J5") (pin "7") (pinfunction "7_7") (pintype "passive"))
      (node (ref "J6") (pin "6") (pinfunction "6_6") (pintype "passive"))
      (node (ref "R16") (pin "1") (pinfunction "1_1") (pintype "passive"))
      (node (ref "R9") (pin "P4") (pinfunction "1_P4") (pintype "passive"))
    )
    (net (code "57") (name "TXO2") (class "Default")
      (node (ref "J7") (pin "2") (pinfunction "2_2") (pintype "passive"))
      (node (ref "R10") (pin "P8") (pinfunction "2_P8") (pintype "passive"))
    )
    (net (code "58") (name "TXO{slash}PICO") (class "Default")
      (node (ref "J5") (pin "6") (pinfunction "6_6") (pintype "passive"))
      (node (ref "R9") (pin "P1") (pinfunction "1_P1") (pintype "passive"))
    )
    (net (code "59") (name "TX_READY") (class "Default")
      (node (ref "J6") (pin "5") (pinfunction "5_5") (pintype "passive"))
      (node (ref "R8") (pin "P1") (pinfunction "1_P1") (pintype "passive"))
    )
    (net (code "60") (name "VIN") (class "Default")
      (node (ref "C9") (pin "1") (pinfunction "1_1") (pintype "passive"))
      (node (ref "D3") (pin "5") (pinfunction "5_5") (pintype "power_in"))
      (node (ref "J2") (pin "VBUS1") (pinfunction "VBUS_VBUS1") (pintype "bidirectional"))
      (node (ref "J2") (pin "VBUS2") (pinfunction "VBUS_VBUS2") (pintype "bidirectional"))
      (node (ref "J5") (pin "2") (pinfunction "2_2") (pintype "passive"))
      (node (ref "U5") (pin "1") (pinfunction "IN_1") (pintype "input"))
      (node (ref "U5") (pin "3") (pinfunction "EN_3") (pintype "input"))
    )
    (net (code "61") (name "V_BATT") (class "Default")
      (node (ref "BT2") (pin "+") (pinfunction "+_+") (pintype "power_in"))
      (node (ref "C11") (pin "1") (pinfunction "1_1") (pintype "passive"))
      (node (ref "R24") (pin "1") (pinfunction "1_1") (pintype "passive"))
      (node (ref "TP1") (pin "1") (pinfunction "1_1") (pintype "bidirectional"))
      (node (ref "U6") (pin "P36") (pinfunction "V_BKCP_P36") (pintype "power_in"))
    )
    (net (code "62") (name "V_RF") (class "Default")
      (node (ref "R13") (pin "2") (pinfunction "2_2") (pintype "passive"))
      (node (ref "U6") (pin "P7") (pinfunction "V_RF_P7") (pintype "output"))
    )
    (net (code "63") (name "WT+") (class "Default")
      (node (ref "J5") (pin "11") (pinfunction "11_11") (pintype "passive"))
      (node (ref "R2") (pin "1") (pinfunction "1_1") (pintype "passive"))
    )
    (net (code "64") (name "WT_IN") (class "Default")
      (node (ref "R6") (pin "2") (pinfunction "2_2") (pintype "passive"))
      (node (ref "U1") (pin "1") (pinfunction "ANODE1_1") (pintype "input"))
    )
    (net (code "65") (name "WT_INV") (class "Default")
      (node (ref "R7") (pin "1") (pinfunction "1_1") (pintype "passive"))
      (node (ref "U1") (pin "7") (pinfunction "VOUT1_7") (pintype "output"))
      (node (ref "U3") (pin "P2") (pinfunction "A_P2") (pintype "input"))
    )
    (net (code "66") (name "WT_OUT") (class "Default")
      (node (ref "R10") (pin "P5") (pinfunction "2_P5") (pintype "passive"))
      (node (ref "U3") (pin "P4") (pinfunction "Y_P4") (pintype "output"))
    )
    (net (code "67") (name "unconnected-(J7-Pad1)") (class "Default")
      (node (ref "J7") (pin "1") (pinfunction "1_1") (pintype "passive"))
    )
    (net (code "68") (name "unconnected-(J7-Pad4)") (class "Default")
      (node (ref "J7") (pin "4") (pinfunction "4_4") (pintype "passive"))
    )
    (net (code "69") (name "unconnected-(J7-Pad5)") (class "Default")
      (node (ref "J7") (pin "5") (pinfunction "5_5") (pintype "passive"))
    )
    (net (code "70") (name "unconnected-(U6-ANT_DETECT-PadP4)") (class "Default")
      (node (ref "U6") (pin "P4") (pinfunction "ANT_DETECT_P4") (pintype "input"))
    )
    (net (code "71") (name "unconnected-(U6-ANT_OFF-PadP5)") (class "Default")
      (node (ref "U6") (pin "P5") (pinfunction "ANT_OFF_P5") (pintype "output"))
    )
    (net (code "72") (name "unconnected-(U6-~{ANT_SHORT}-PadP6)") (class "Default")
      (node (ref "U6") (pin "P6") (pinfunction "~{ANT_SHORT}_P6") (pintype "output"))
    )
  )
)
